# Connector.net
KiCad netlist of a schematic drawn in Altium Designer
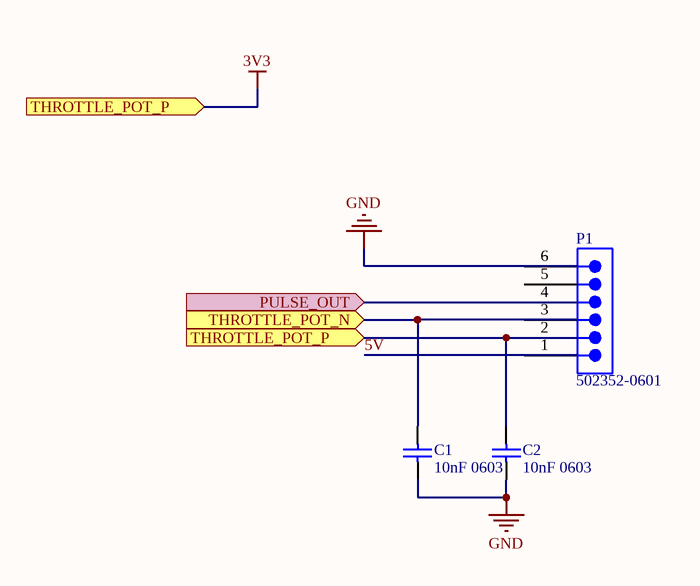
[diagram p0: Connector.SchDoc]

(export (version "E")
  (design (tool "Eeschema 10.0.6"))
  (components
    (comp (ref "C1")
      (value "10nF 0603")
      (footprint "CAPC0603(1608)100_N")
      (description "CAP 10nF 100V ±10% 0603 (1608 Metric) Thickness 1mm SMD")
      (fields (field (name "TOLERANCE") "Â±10%"))
      (libsource (lib "Altium Content Vault") (part "CAP"))
    )
    (comp (ref "C2")
      (value "10nF 0603")
      (footprint "CAPC0603(1608)100_N")
      (description "CAP 10nF 100V ±10% 0603 (1608 Metric) Thickness 1mm SMD")
      (fields (field (name "TOLERANCE") "Â±10%"))
      (libsource (lib "Altium Content Vault") (part "CAP"))
    )
    (comp (ref "P1")
      (value "502352-0601")
      (footprint "502352-0601")
      (libsource (lib "EV_library") (part "502352-0601"))
    )
  )
  (nets
    (net (code "1") (name "/5V") (class "Default")
      (node (ref "P1") (pin "1") (pinfunction "1_1") (pintype "passive"))
    )
    (net (code "2") (name "/PULSE_OUT") (class "Default")
      (node (ref "P1") (pin "4") (pinfunction "4_4") (pintype "passive"))
    )
    (net (code "3") (name "/THROTTLE_POT_N") (class "Default")
      (node (ref "C1") (pin "2") (pinfunction "2_2") (pintype "passive"))
      (node (ref "P1") (pin "3") (pinfunction "3_3") (pintype "passive"))
    )
    (net (code "4") (name "3V3") (class "Default")
      (node (ref "C2") (pin "2") (pinfunction "2_2") (pintype "passive"))
      (node (ref "P1") (pin "2") (pinfunction "2_2") (pintype "passive"))
    )
    (net (code "5") (name "GND") (class "Default")
      (node (ref "C1") (pin "1") (pinfunction "1_1") (pintype "passive"))
      (node (ref "C2") (pin "1") (pinfunction "1_1") (pintype "passive"))
      (node (ref "P1") (pin "6") (pinfunction "6_6") (pintype "passive"))
    )
    (net (code "6") (name "unconnected-(P1-Pad5)") (class "Default")
      (node (ref "P1") (pin "5") (pinfunction "5_5") (pintype "passive"))
    )
  )
)
